# CH32L103K8U6-R0.net
KiCad netlist of a schematic drawn in Altium Designer
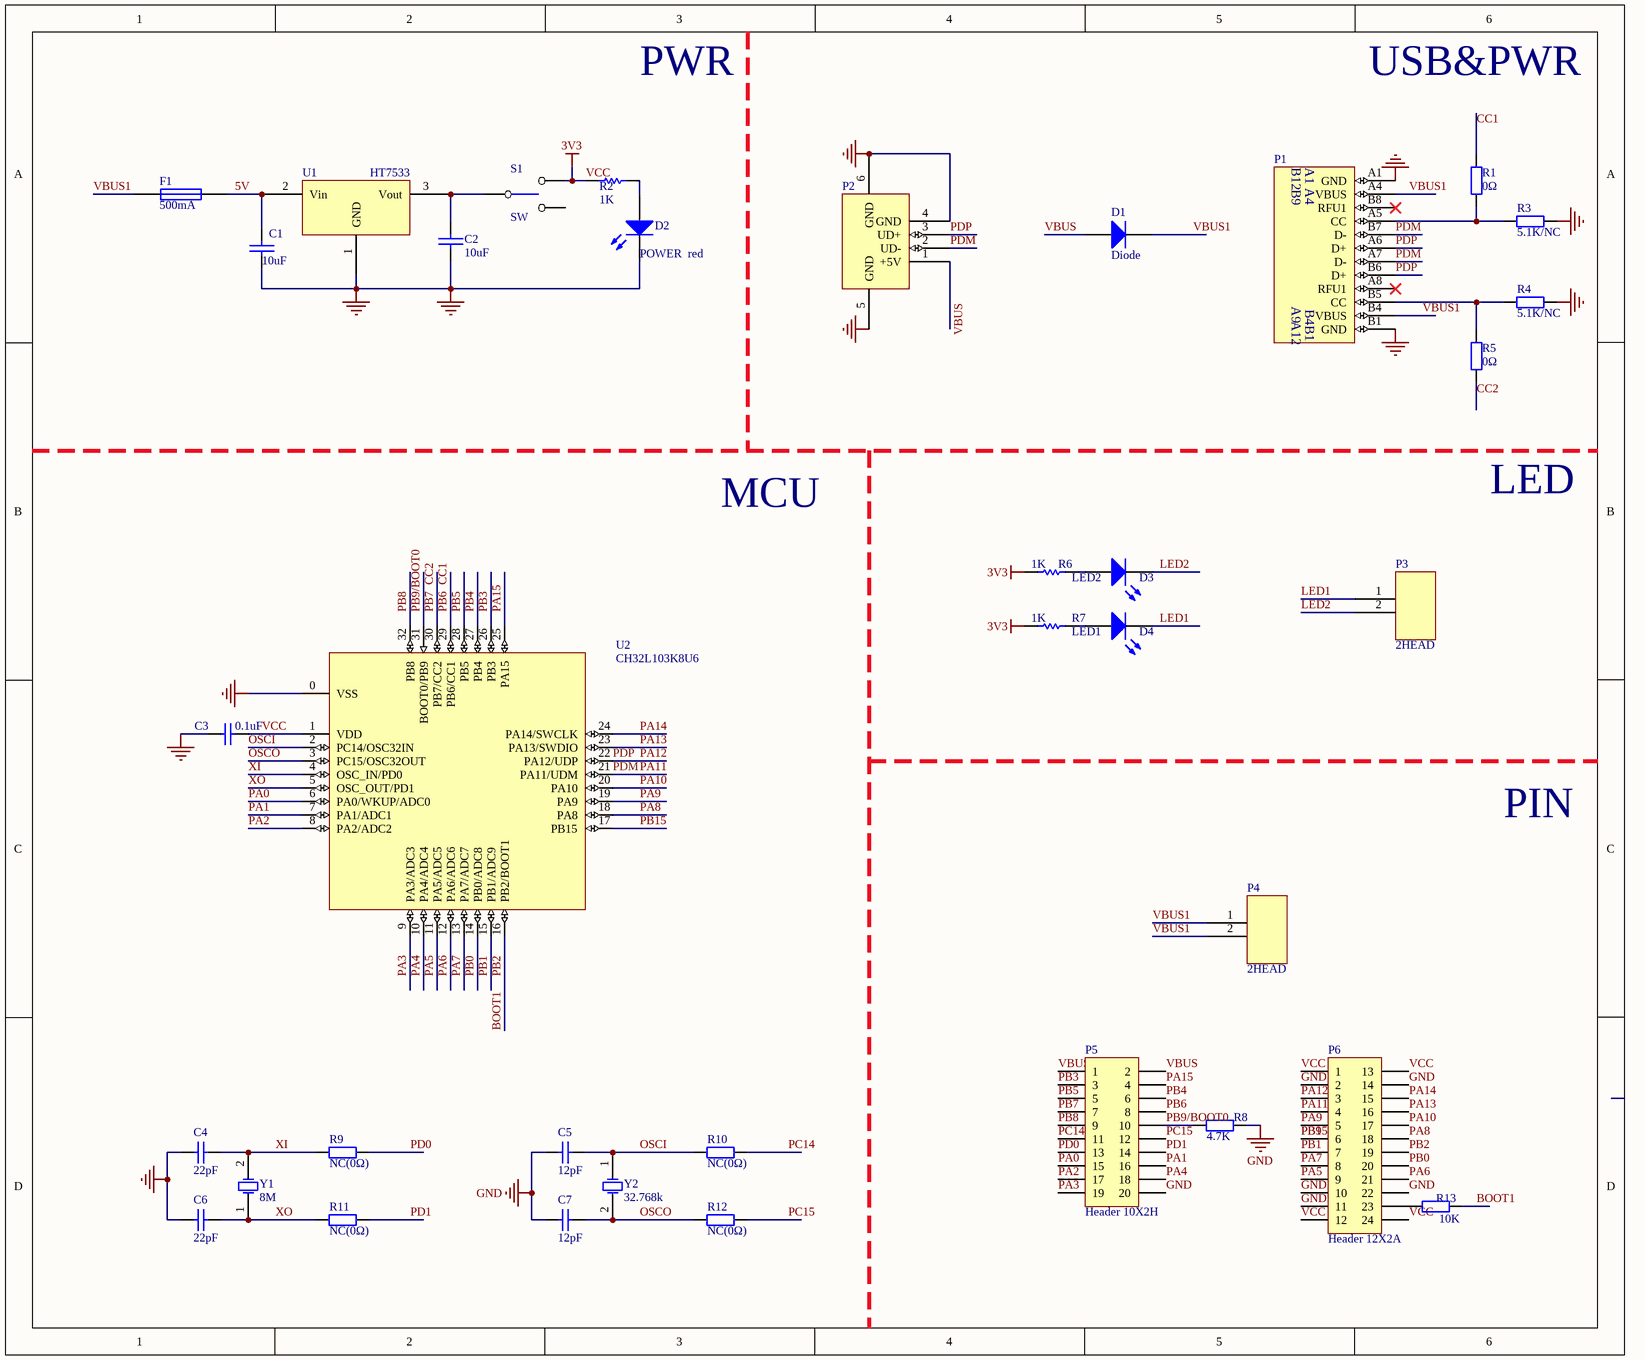
[diagram p0: CH32L103K8U6-R0.SchDoc]

(export (version "E")
  (design (tool "Eeschema 10.0.6"))
  (components
    (comp (ref "C1")
      (value "10uF")
      (footprint "0603_C")
      (description "Capacitor")
      (libsource (lib "*") (part "CAP"))
    )
    (comp (ref "C2")
      (value "10uF")
      (footprint "0603_C")
      (description "Capacitor")
      (libsource (lib "*") (part "CAP"))
    )
    (comp (ref "C3")
      (value "0.1uF")
      (footprint "0603_C")
      (description "Capacitor")
      (fields (field (name "PUBLISHER") "Altium Limited"))
      (libsource (lib "*") (part "Cap"))
    )
    (comp (ref "C4")
      (value "22pF")
      (footprint "0603_C")
      (description "Capacitor")
      (fields (field (name "PUBLISHER") "Altium Limited"))
      (libsource (lib "*") (part "Cap"))
    )
    (comp (ref "C5")
      (value "12pF")
      (footprint "0603")
      (description "Capacitor")
      (fields (field (name "PUBLISHER") "Altium Limited"))
      (libsource (lib "Miscellaneous Devices") (part "Cap"))
    )
    (comp (ref "C6")
      (value "22pF")
      (footprint "0603_C")
      (description "Capacitor")
      (fields (field (name "PUBLISHER") "Altium Limited"))
      (libsource (lib "*") (part "Cap"))
    )
    (comp (ref "C7")
      (value "12pF")
      (footprint "0603")
      (description "Capacitor")
      (fields (field (name "PUBLISHER") "Altium Limited"))
      (libsource (lib "Miscellaneous Devices") (part "Cap"))
    )
    (comp (ref "D1")
      (value "Diode")
      (footprint "SOD-123")
      (description "Default Diode")
      (fields (field (name "PUBLISHER") "Altium Limited"))
      (libsource (lib "Miscellaneous Devices") (part "Diode"))
    )
    (comp (ref "D2")
      (value "POWER  red")
      (footprint "0603+")
      (description "Typical INFRARED GaAs LED")
      (fields (field (name "PUBLISHER") "Altium Limited"))
      (libsource (lib "*") (part "LED0"))
    )
    (comp (ref "D3")
      (value "LED2")
      (footprint "0603+")
      (description "Typical INFRARED GaAs LED")
      (fields (field (name "PUBLISHER") "Altium Limited"))
      (libsource (lib "*") (part "LED0"))
    )
    (comp (ref "D4")
      (value "LED1")
      (footprint "0603+")
      (description "Typical INFRARED GaAs LED")
      (fields (field (name "PUBLISHER") "Altium Limited"))
      (libsource (lib "*") (part "LED0"))
    )
    (comp (ref "F1")
      (value "500mA")
      (footprint "0603")
      (description "Fuse")
      (libsource (lib "*") (part "FUSE1"))
    )
    (comp (ref "P1")
      (value "TYPE-C")
      (footprint "TYPE-C-Receptacle-2.0")
      (libsource (lib "*") (part "TYPE-C1"))
    )
    (comp (ref "P2")
      (value "USB_A")
      (footprint "USBAF")
      (description "USB Port")
      (libsource (lib "*") (part "USB"))
    )
    (comp (ref "P3") (value "2HEAD") (footprint "SIP2-2.54mm") (libsource (lib "*") (part "2HEAD")))
    (comp (ref "P4") (value "2HEAD") (footprint "SIP2-2.54mm") (libsource (lib "*") (part "2HEAD")))
    (comp (ref "P5")
      (value "Header 10X2H")
      (footprint "HDR2X10H")
      (description "Header, 10-Pin, Dual row, Right Angle")
      (fields (field (name "PUBLISHER") "Altium Limited"))
      (libsource (lib "Miscellaneous Connectors") (part "Header 10X2H"))
    )
    (comp (ref "P6")
      (value "Header 12X2A")
      (footprint "HDR2X12_CEN")
      (description "Header, 12-Pin, Dual row")
      (fields (field (name "PUBLISHER") "Altium Limited"))
      (libsource (lib "Miscellaneous Connectors") (part "Header 12X2A"))
    )
    (comp (ref "R1")
      (value "0Ω")
      (footprint "0603")
      (description "Resistor")
      (libsource (lib "") (part "Res2_1"))
    )
    (comp (ref "R2")
      (value "1K")
      (footprint "0603")
      (description "Semiconductor Resistor")
      (libsource (lib "*") (part "Res Semi"))
    )
    (comp (ref "R3")
      (value "5.1K/NC")
      (footprint "0603")
      (description "Resistor")
      (libsource (lib "") (part "Res2_2"))
    )
    (comp (ref "R4")
      (value "5.1K/NC")
      (footprint "0603")
      (description "Resistor")
      (libsource (lib "") (part "Res2_2"))
    )
    (comp (ref "R5")
      (value "0Ω")
      (footprint "0603")
      (description "Resistor")
      (libsource (lib "") (part "Res2_1"))
    )
    (comp (ref "R6")
      (value "1K")
      (footprint "0603")
      (description "Semiconductor Resistor")
      (libsource (lib "*") (part "Res Semi"))
    )
    (comp (ref "R7")
      (value "1K")
      (footprint "0603")
      (description "Semiconductor Resistor")
      (libsource (lib "*") (part "Res Semi"))
    )
    (comp (ref "R8")
      (value "4.7K")
      (footprint "0603")
      (description "Resistor")
      (libsource (lib "") (part "Res2_2"))
    )
    (comp (ref "R9")
      (value "NC(0Ω)")
      (footprint "0603")
      (description "Resistor")
      (libsource (lib "Miscellaneous Devices") (part "Res2"))
    )
    (comp (ref "R10")
      (value "NC(0Ω)")
      (footprint "0603")
      (description "Resistor")
      (libsource (lib "Miscellaneous Devices") (part "Res2"))
    )
    (comp (ref "R11")
      (value "NC(0Ω)")
      (footprint "0603")
      (description "Resistor")
      (libsource (lib "Miscellaneous Devices") (part "Res2"))
    )
    (comp (ref "R12")
      (value "NC(0Ω)")
      (footprint "0603")
      (description "Resistor")
      (libsource (lib "Miscellaneous Devices") (part "Res2"))
    )
    (comp (ref "R13")
      (value "10K")
      (footprint "0603")
      (description "Resistor")
      (fields (field (name "PUBLISHER") "Altium Limited"))
      (libsource (lib "*") (part "Res2"))
    )
    (comp (ref "S1") (value "SW") (footprint "SW1") (libsource (lib "*") (part "SW")))
    (comp (ref "U1")
      (value "HT7533")
      (footprint "SOT-89")
      (libsource (lib "wch_sch_others") (part "1117-3.3V"))
    )
    (comp (ref "U2")
      (value "CH32L103K8U6")
      (footprint "QFN32_4X4")
      (description "RISC-V LMD-MCU, 96MHz, USB, Type-C/PD-5K1, CAN, OPA, lower power")
      (libsource (lib "CHXXX") (part "CH32L103K8U6"))
    )
    (comp (ref "Y1")
      (value "8M")
      (footprint "XT_AT49")
      (description "Crystal Oscillator")
      (fields (field (name "PUBLISHER") "Altium Limited"))
      (libsource (lib "*") (part "XTAL"))
    )
    (comp (ref "Y2")
      (value "32.768k")
      (footprint "FC-135")
      (description "Crystal Oscillator")
      (fields (field (name "PUBLISHER") "Altium Limited"))
      (libsource (lib "Miscellaneous Devices") (part "XTAL"))
    )
  )
  (nets
    (net (code "1") (name "/5V") (class "Default")
      (node (ref "C1") (pin "1") (pinfunction "1_1") (pintype "passive"))
      (node (ref "F1") (pin "2") (pinfunction "2_2") (pintype "passive"))
      (node (ref "U1") (pin "2") (pinfunction "Vin_2") (pintype "passive"))
    )
    (net (code "3") (name "/BOOT1") (class "Default")
      (node (ref "P6") (pin "19") (pinfunction "19_19") (pintype "passive"))
      (node (ref "R13") (pin "2") (pinfunction "2_2") (pintype "passive"))
      (node (ref "U2") (pin "16") (pinfunction "PB2/BOOT1_16") (pintype "bidirectional"))
    )
    (net (code "4") (name "/CC1") (class "Default")
      (node (ref "P5") (pin "8") (pinfunction "8_8") (pintype "passive"))
      (node (ref "R1") (pin "2") (pinfunction "2_2") (pintype "passive"))
      (node (ref "U2") (pin "29") (pinfunction "PB6/CC1_29") (pintype "bidirectional"))
    )
    (net (code "5") (name "/CC2") (class "Default")
      (node (ref "P5") (pin "7") (pinfunction "7_7") (pintype "passive"))
      (node (ref "R5") (pin "1") (pinfunction "1_1") (pintype "passive"))
      (node (ref "U2") (pin "30") (pinfunction "PB7/CC2_30") (pintype "bidirectional"))
    )
    (net (code "6") (name "/LED1") (class "Default")
      (node (ref "D4") (pin "2") (pinfunction "K_2") (pintype "passive"))
      (node (ref "P3") (pin "1") (pintype "passive"))
    )
    (net (code "7") (name "/LED2") (class "Default")
      (node (ref "D3") (pin "2") (pinfunction "K_2") (pintype "passive"))
      (node (ref "P3") (pin "2") (pintype "passive"))
    )
    (net (code "8") (name "/OSCI") (class "Default")
      (node (ref "C5") (pin "1") (pinfunction "1_1") (pintype "passive"))
      (node (ref "R10") (pin "2") (pinfunction "2_2") (pintype "passive"))
      (node (ref "U2") (pin "2") (pinfunction "PC14/OSC32IN_2") (pintype "bidirectional"))
      (node (ref "Y2") (pin "1") (pinfunction "OSC1_1") (pintype "passive"))
    )
    (net (code "9") (name "/OSCO") (class "Default")
      (node (ref "C7") (pin "1") (pinfunction "1_1") (pintype "passive"))
      (node (ref "R12") (pin "2") (pinfunction "2_2") (pintype "passive"))
      (node (ref "U2") (pin "3") (pinfunction "PC15/OSC32OUT_3") (pintype "bidirectional"))
      (node (ref "Y2") (pin "2") (pinfunction "OSC2_2") (pintype "passive"))
    )
    (net (code "10") (name "/PA0") (class "Default")
      (node (ref "P5") (pin "15") (pinfunction "15_15") (pintype "passive"))
      (node (ref "U2") (pin "6") (pinfunction "PA0/WKUP/ADC0_6") (pintype "bidirectional"))
    )
    (net (code "11") (name "/PA1") (class "Default")
      (node (ref "P5") (pin "16") (pinfunction "16_16") (pintype "passive"))
      (node (ref "U2") (pin "7") (pinfunction "PA1/ADC1_7") (pintype "bidirectional"))
    )
    (net (code "12") (name "/PA2") (class "Default")
      (node (ref "P5") (pin "17") (pinfunction "17_17") (pintype "passive"))
      (node (ref "U2") (pin "8") (pinfunction "PA2/ADC2_8") (pintype "bidirectional"))
    )
    (net (code "13") (name "/PA3") (class "Default")
      (node (ref "P5") (pin "19") (pinfunction "19_19") (pintype "passive"))
      (node (ref "U2") (pin "9") (pinfunction "PA3/ADC3_9") (pintype "bidirectional"))
    )
    (net (code "14") (name "/PA4") (class "Default")
      (node (ref "P5") (pin "18") (pinfunction "18_18") (pintype "passive"))
      (node (ref "U2") (pin "10") (pinfunction "PA4/ADC4_10") (pintype "bidirectional"))
    )
    (net (code "15") (name "/PA5") (class "Default")
      (node (ref "P6") (pin "9") (pinfunction "9_9") (pintype "passive"))
      (node (ref "U2") (pin "11") (pinfunction "PA5/ADC5_11") (pintype "bidirectional"))
    )
    (net (code "16") (name "/PA6") (class "Default")
      (node (ref "P6") (pin "21") (pinfunction "21_21") (pintype "passive"))
      (node (ref "U2") (pin "12") (pinfunction "PA6/ADC6_12") (pintype "bidirectional"))
    )
    (net (code "17") (name "/PA7") (class "Default")
      (node (ref "P6") (pin "8") (pinfunction "8_8") (pintype "passive"))
      (node (ref "U2") (pin "13") (pinfunction "PA7/ADC7_13") (pintype "bidirectional"))
    )
    (net (code "18") (name "/PA8") (class "Default")
      (node (ref "P6") (pin "18") (pinfunction "18_18") (pintype "passive"))
      (node (ref "U2") (pin "18") (pinfunction "PA8_18") (pintype "bidirectional"))
    )
    (net (code "19") (name "/PA9") (class "Default")
      (node (ref "P6") (pin "5") (pinfunction "5_5") (pintype "passive"))
      (node (ref "U2") (pin "19") (pinfunction "PA9_19") (pintype "bidirectional"))
    )
    (net (code "20") (name "/PA10") (class "Default")
      (node (ref "P6") (pin "17") (pinfunction "17_17") (pintype "passive"))
      (node (ref "U2") (pin "20") (pinfunction "PA10_20") (pintype "bidirectional"))
    )
    (net (code "21") (name "/PA11") (class "Default")
      (node (ref "P1") (pin "A7") (pinfunction "D-_A7") (pintype "bidirectional"))
      (node (ref "P1") (pin "B7") (pinfunction "D-_B7") (pintype "bidirectional"))
      (node (ref "P2") (pin "2") (pinfunction "UD-_2") (pintype "bidirectional"))
      (node (ref "P6") (pin "4") (pinfunction "4_4") (pintype "passive"))
      (node (ref "U2") (pin "21") (pinfunction "PA11/UDM_21") (pintype "bidirectional"))
    )
    (net (code "22") (name "/PA12") (class "Default")
      (node (ref "P1") (pin "A6") (pinfunction "D+_A6") (pintype "bidirectional"))
      (node (ref "P1") (pin "B6") (pinfunction "D+_B6") (pintype "bidirectional"))
      (node (ref "P2") (pin "3") (pinfunction "UD+_3") (pintype "bidirectional"))
      (node (ref "P6") (pin "3") (pinfunction "3_3") (pintype "passive"))
      (node (ref "U2") (pin "22") (pinfunction "PA12/UDP_22") (pintype "bidirectional"))
    )
    (net (code "23") (name "/PA13") (class "Default")
      (node (ref "P6") (pin "16") (pinfunction "16_16") (pintype "passive"))
      (node (ref "U2") (pin "23") (pinfunction "PA13/SWDIO_23") (pintype "bidirectional"))
    )
    (net (code "24") (name "/PA14") (class "Default")
      (node (ref "P6") (pin "15") (pinfunction "15_15") (pintype "passive"))
      (node (ref "U2") (pin "24") (pinfunction "PA14/SWCLK_24") (pintype "bidirectional"))
    )
    (net (code "25") (name "/PA15") (class "Default")
      (node (ref "P5") (pin "4") (pinfunction "4_4") (pintype "passive"))
      (node (ref "U2") (pin "25") (pinfunction "PA15_25") (pintype "bidirectional"))
    )
    (net (code "26") (name "/PB0") (class "Default")
      (node (ref "P6") (pin "20") (pinfunction "20_20") (pintype "passive"))
      (node (ref "U2") (pin "14") (pinfunction "PB0/ADC8_14") (pintype "bidirectional"))
    )
    (net (code "27") (name "/PB1") (class "Default")
      (node (ref "P6") (pin "7") (pinfunction "7_7") (pintype "passive"))
      (node (ref "U2") (pin "15") (pinfunction "PB1/ADC9_15") (pintype "bidirectional"))
    )
    (net (code "28") (name "/PB3") (class "Default")
      (node (ref "P5") (pin "3") (pinfunction "3_3") (pintype "passive"))
      (node (ref "U2") (pin "26") (pinfunction "PB3_26") (pintype "bidirectional"))
    )
    (net (code "29") (name "/PB4") (class "Default")
      (node (ref "P5") (pin "6") (pinfunction "6_6") (pintype "passive"))
      (node (ref "U2") (pin "27") (pinfunction "PB4_27") (pintype "bidirectional"))
    )
    (net (code "30") (name "/PB5") (class "Default")
      (node (ref "P5") (pin "5") (pinfunction "5_5") (pintype "passive"))
      (node (ref "U2") (pin "28") (pinfunction "PB5_28") (pintype "bidirectional"))
    )
    (net (code "31") (name "/PB8") (class "Default")
      (node (ref "P5") (pin "9") (pinfunction "9_9") (pintype "passive"))
      (node (ref "U2") (pin "32") (pinfunction "PB8_32") (pintype "bidirectional"))
    )
    (net (code "32") (name "/PB9{slash}BOOT0") (class "Default")
      (node (ref "P5") (pin "10") (pinfunction "10_10") (pintype "passive"))
      (node (ref "R8") (pin "1") (pinfunction "1_1") (pintype "passive"))
      (node (ref "U2") (pin "31") (pinfunction "BOOT0/PB9_31") (pintype "input"))
    )
    (net (code "33") (name "/PB15") (class "Default")
      (node (ref "P6") (pin "6") (pinfunction "6_6") (pintype "passive"))
      (node (ref "U2") (pin "17") (pinfunction "PB15_17") (pintype "bidirectional"))
    )
    (net (code "34") (name "/PC14") (class "Default")
      (node (ref "P5") (pin "11") (pinfunction "11_11") (pintype "passive"))
      (node (ref "R10") (pin "1") (pinfunction "1_1") (pintype "passive"))
    )
    (net (code "35") (name "/PC15") (class "Default")
      (node (ref "P5") (pin "12") (pinfunction "12_12") (pintype "passive"))
      (node (ref "R12") (pin "1") (pinfunction "1_1") (pintype "passive"))
    )
    (net (code "36") (name "/PD0") (class "Default")
      (node (ref "P5") (pin "13") (pinfunction "13_13") (pintype "passive"))
      (node (ref "R9") (pin "1") (pinfunction "1_1") (pintype "passive"))
    )
    (net (code "37") (name "/PD1") (class "Default")
      (node (ref "P5") (pin "14") (pinfunction "14_14") (pintype "passive"))
      (node (ref "R11") (pin "1") (pinfunction "1_1") (pintype "passive"))
    )
    (net (code "38") (name "/VBUS") (class "Default")
      (node (ref "D1") (pin "1") (pinfunction "A_1") (pintype "passive"))
      (node (ref "P2") (pin "1") (pinfunction "+5V_1") (pintype "power_in"))
      (node (ref "P5") (pin "1") (pinfunction "1_1") (pintype "passive"))
      (node (ref "P5") (pin "2") (pinfunction "2_2") (pintype "passive"))
    )
    (net (code "39") (name "/VBUS1") (class "Default")
      (node (ref "D1") (pin "2") (pinfunction "K_2") (pintype "passive"))
      (node (ref "F1") (pin "1") (pinfunction "1_1") (pintype "passive"))
      (node (ref "P1") (pin "A4") (pinfunction "VBUS_A4") (pintype "bidirectional"))
      (node (ref "P1") (pin "B4") (pinfunction "VBUS_B4") (pintype "bidirectional"))
      (node (ref "P4") (pin "1") (pintype "passive"))
      (node (ref "P4") (pin "2") (pintype "passive"))
    )
    (net (code "40") (name "/XI") (class "Default")
      (node (ref "C4") (pin "2") (pinfunction "2_2") (pintype "passive"))
      (node (ref "R9") (pin "2") (pinfunction "2_2") (pintype "passive"))
      (node (ref "U2") (pin "4") (pinfunction "OSC_IN/PD0_4") (pintype "bidirectional"))
      (node (ref "Y1") (pin "2") (pinfunction "OSC2_2") (pintype "passive"))
    )
    (net (code "41") (name "/XO") (class "Default")
      (node (ref "C6") (pin "2") (pinfunction "2_2") (pintype "passive"))
      (node (ref "R11") (pin "2") (pinfunction "2_2") (pintype "passive"))
      (node (ref "U2") (pin "5") (pinfunction "OSC_OUT/PD1_5") (pintype "bidirectional"))
      (node (ref "Y1") (pin "1") (pinfunction "OSC1_1") (pintype "passive"))
    )
    (net (code "42") (name "3V3") (class "Default")
      (node (ref "C3") (pin "1") (pinfunction "1_1") (pintype "passive"))
      (node (ref "P6") (pin "1") (pinfunction "1_1") (pintype "passive"))
      (node (ref "P6") (pin "12") (pinfunction "12_12") (pintype "passive"))
      (node (ref "P6") (pin "13") (pinfunction "13_13") (pintype "passive"))
      (node (ref "P6") (pin "24") (pinfunction "24_24") (pintype "passive"))
      (node (ref "R2") (pin "2") (pinfunction "2_2") (pintype "passive"))
      (node (ref "R6") (pin "1") (pinfunction "1_1") (pintype "passive"))
      (node (ref "R7") (pin "1") (pinfunction "1_1") (pintype "passive"))
      (node (ref "S1") (pin "3") (pinfunction "3_3") (pintype "passive"))
      (node (ref "U2") (pin "1") (pinfunction "VDD_1") (pintype "power_in"))
    )
    (net (code "43") (name "GND") (class "Default")
      (node (ref "C1") (pin "2") (pinfunction "2_2") (pintype "passive"))
      (node (ref "C2") (pin "2") (pinfunction "2_2") (pintype "passive"))
      (node (ref "C3") (pin "2") (pinfunction "2_2") (pintype "passive"))
      (node (ref "C4") (pin "1") (pinfunction "1_1") (pintype "passive"))
      (node (ref "C5") (pin "2") (pinfunction "2_2") (pintype "passive"))
      (node (ref "C6") (pin "1") (pinfunction "1_1") (pintype "passive"))
      (node (ref "C7") (pin "2") (pinfunction "2_2") (pintype "passive"))
      (node (ref "D2") (pin "2") (pinfunction "K_2") (pintype "passive"))
      (node (ref "P1") (pin "A1") (pinfunction "GND_A1") (pintype "bidirectional"))
      (node (ref "P1") (pin "B1") (pinfunction "GND_B1") (pintype "bidirectional"))
      (node (ref "P2") (pin "4") (pinfunction "GND_4") (pintype "power_in"))
      (node (ref "P2") (pin "5") (pinfunction "GND_5") (pintype "power_in"))
      (node (ref "P2") (pin "6") (pinfunction "GND_6") (pintype "power_in"))
      (node (ref "P5") (pin "20") (pinfunction "20_20") (pintype "passive"))
      (node (ref "P6") (pin "10") (pinfunction "10_10") (pintype "passive"))
      (node (ref "P6") (pin "11") (pinfunction "11_11") (pintype "passive"))
      (node (ref "P6") (pin "14") (pinfunction "14_14") (pintype "passive"))
      (node (ref "P6") (pin "2") (pinfunction "2_2") (pintype "passive"))
      (node (ref "P6") (pin "22") (pinfunction "22_22") (pintype "passive"))
      (node (ref "R3") (pin "2") (pinfunction "2_2") (pintype "passive"))
      (node (ref "R4") (pin "2") (pinfunction "2_2") (pintype "passive"))
      (node (ref "R8") (pin "2") (pinfunction "2_2") (pintype "passive"))
      (node (ref "U1") (pin "1") (pinfunction "GND_1") (pintype "passive"))
      (node (ref "U2") (pin "0") (pinfunction "VSS_0") (pintype "power_in"))
    )
    (net (code "44") (name "Net-(D2-A)") (class "Default")
      (node (ref "D2") (pin "1") (pinfunction "A_1") (pintype "passive"))
      (node (ref "R2") (pin "1") (pinfunction "1_1") (pintype "passive"))
    )
    (net (code "45") (name "Net-(D3-A)") (class "Default")
      (node (ref "D3") (pin "1") (pinfunction "A_1") (pintype "passive"))
      (node (ref "R6") (pin "2") (pinfunction "2_2") (pintype "passive"))
    )
    (net (code "46") (name "Net-(D4-A)") (class "Default")
      (node (ref "D4") (pin "1") (pinfunction "A_1") (pintype "passive"))
      (node (ref "R7") (pin "2") (pinfunction "2_2") (pintype "passive"))
    )
    (net (code "47") (name "Net-(P1-CC-PadA5)") (class "Default")
      (node (ref "P1") (pin "A5") (pinfunction "CC_A5") (pintype "bidirectional"))
      (node (ref "R1") (pin "1") (pinfunction "1_1") (pintype "passive"))
      (node (ref "R3") (pin "1") (pinfunction "1_1") (pintype "passive"))
    )
    (net (code "48") (name "Net-(P1-CC-PadB5)") (class "Default")
      (node (ref "P1") (pin "B5") (pinfunction "CC_B5") (pintype "bidirectional"))
      (node (ref "R4") (pin "1") (pinfunction "1_1") (pintype "passive"))
      (node (ref "R5") (pin "2") (pinfunction "2_2") (pintype "passive"))
    )
    (net (code "49") (name "Net-(P6-Pad23)") (class "Default")
      (node (ref "P6") (pin "23") (pinfunction "23_23") (pintype "passive"))
      (node (ref "R13") (pin "1") (pinfunction "1_1") (pintype "passive"))
    )
    (net (code "50") (name "Net-(U1-Vout)") (class "Default")
      (node (ref "C2") (pin "1") (pinfunction "1_1") (pintype "passive"))
      (node (ref "S1") (pin "1") (pinfunction "1_1") (pintype "passive"))
      (node (ref "U1") (pin "3") (pinfunction "Vout_3") (pintype "passive"))
    )
    (net (code "51") (name "unconnected-(P1-RFU1-PadA8)") (class "Default")
      (node (ref "P1") (pin "A8") (pinfunction "RFU1_A8") (pintype "bidirectional+no_connect"))
    )
    (net (code "52") (name "unconnected-(P1-RFU1-PadB8)") (class "Default")
      (node (ref "P1") (pin "B8") (pinfunction "RFU1_B8") (pintype "bidirectional+no_connect"))
    )
    (net (code "53") (name "unconnected-(S1-Pad2)") (class "Default")
      (node (ref "S1") (pin "2") (pinfunction "2_2") (pintype "passive"))
    )
  )
)
